# GNSS.net
KiCad netlist of a schematic drawn in Altium Designer
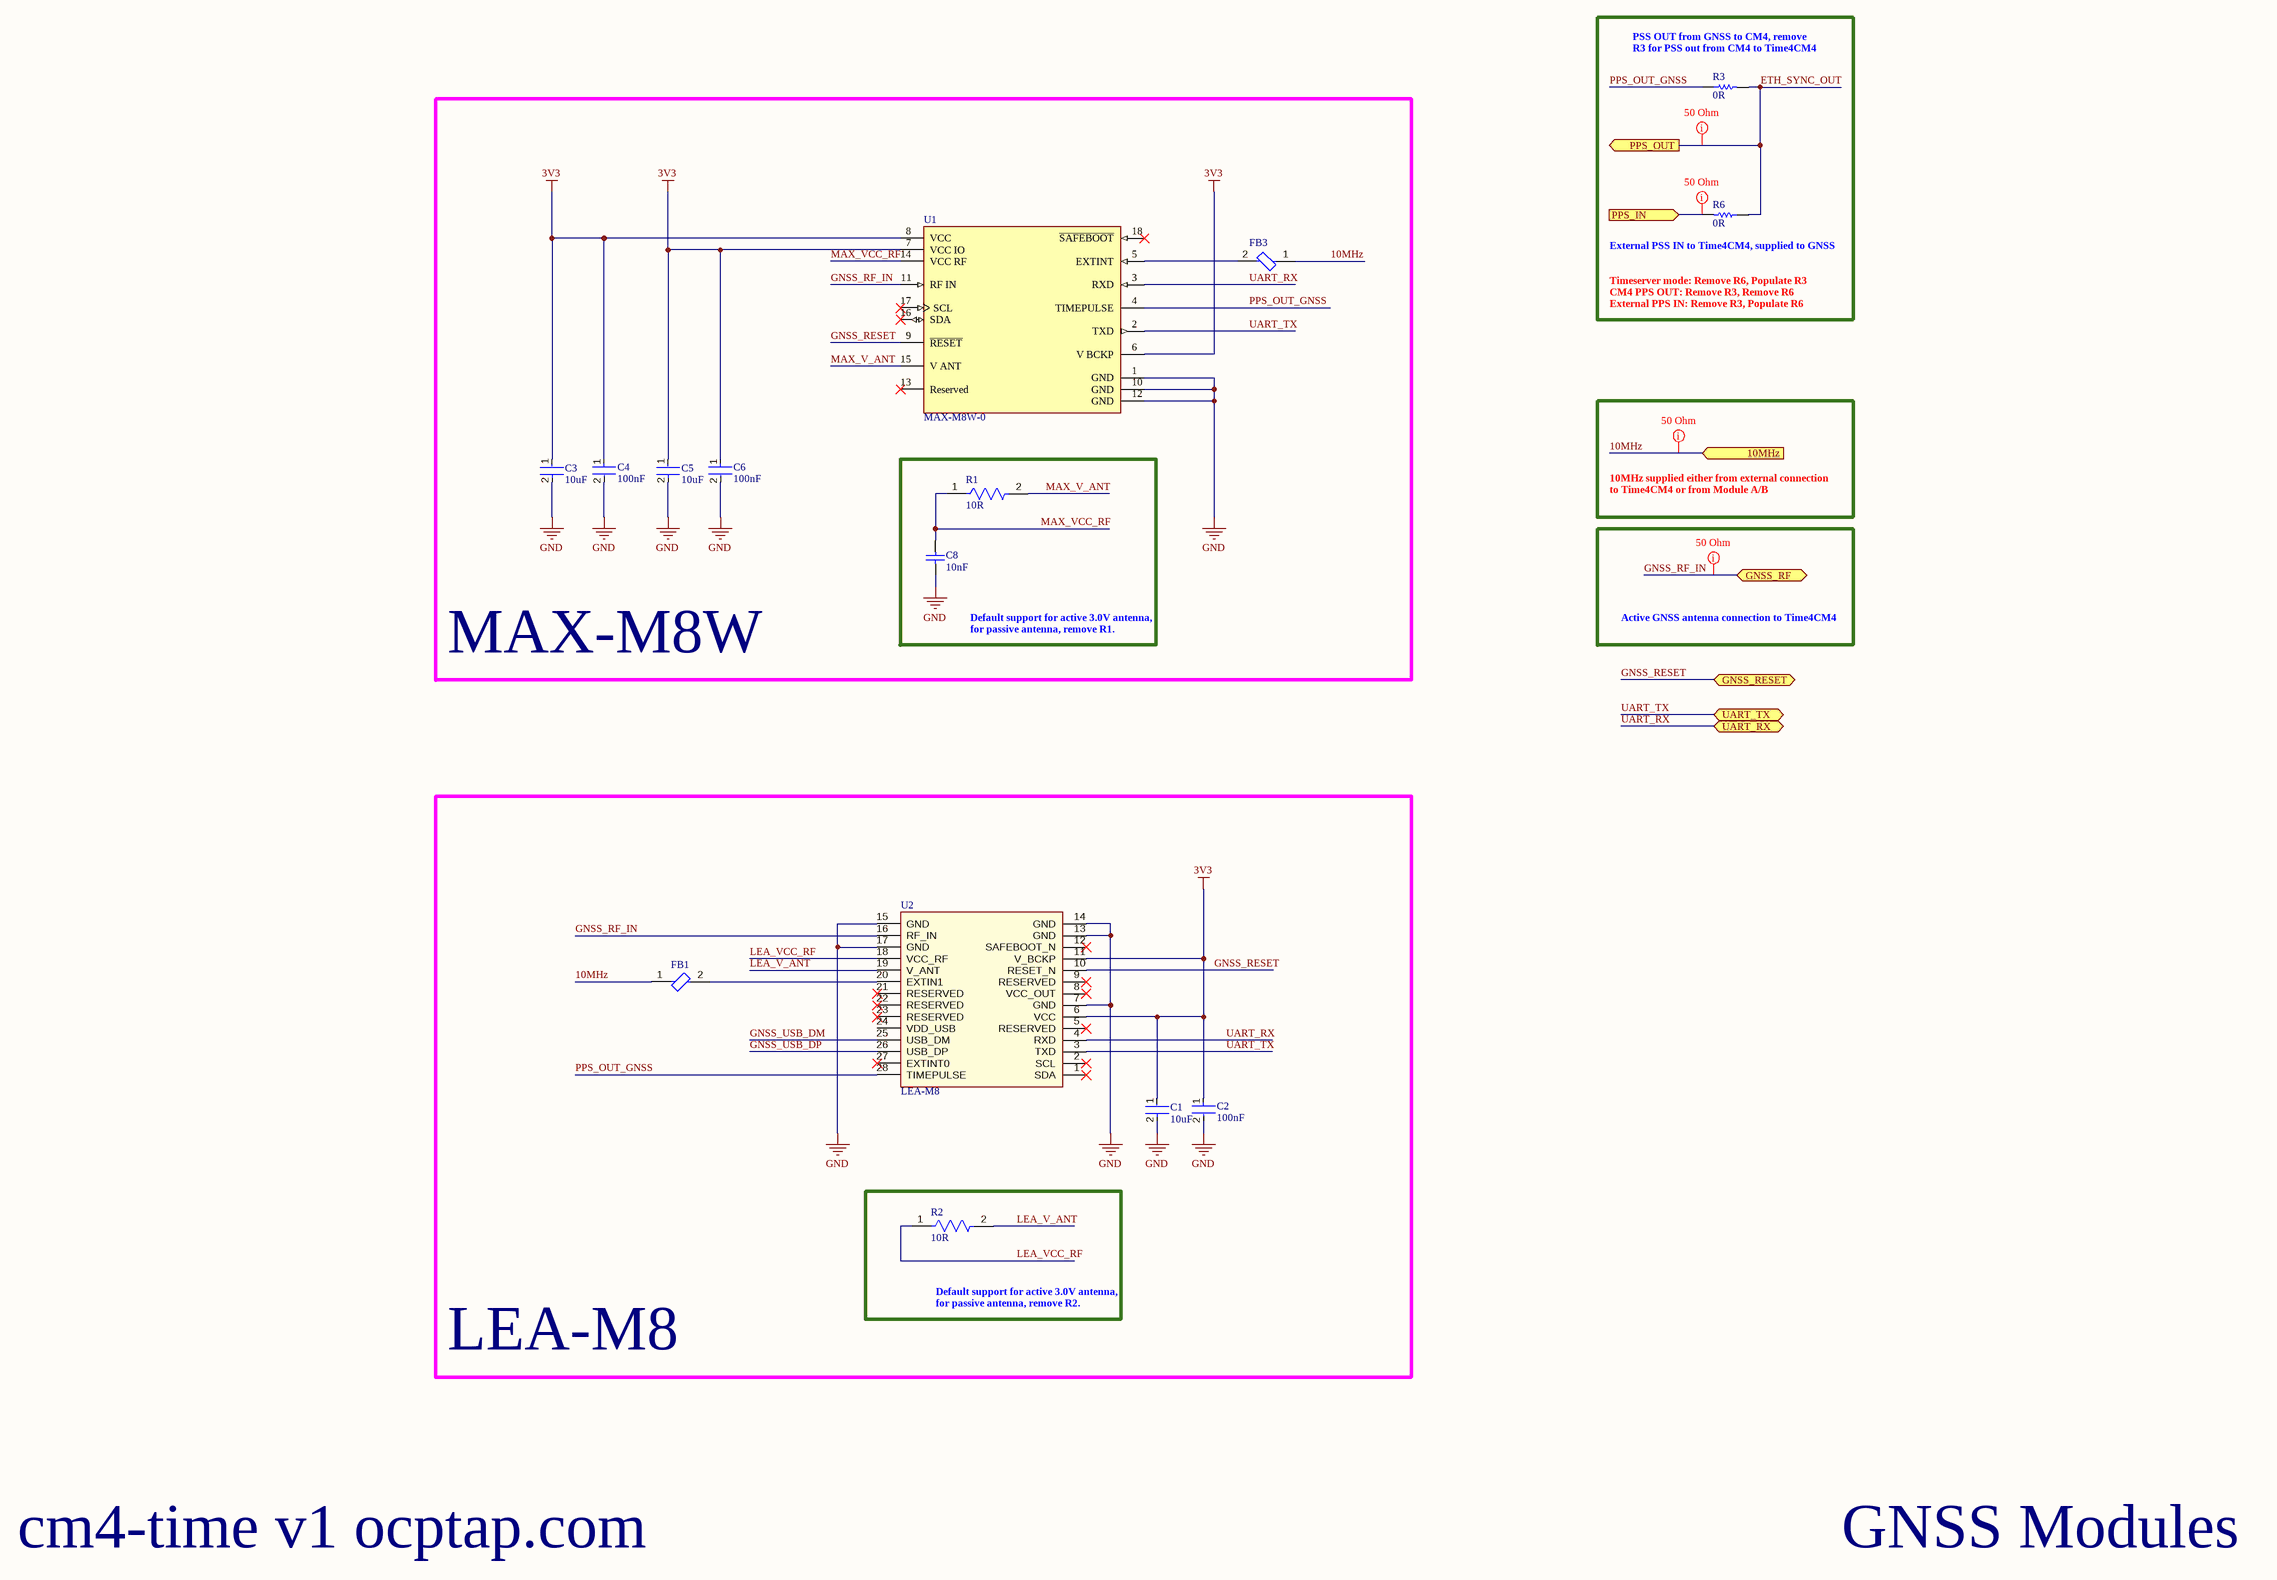
[diagram p0: GNSS.SchDoc]

(export (version "E")
  (design (tool "Eeschema 10.0.6"))
  (components
    (comp (ref "C1")
      (value "10uF")
      (footprint "FP-C1608-080-0_1-IPC_A")
      (description "Multilayer Ceramic Capacitors 10μF ±10% 10V X5R SMD 0603")
      (fields (field (name "VOLTAGE") "10V") (field (name "TOLERANCE") "10%"))
      (libsource (lib "Altium Content Vault") (part "236180d848d6139a670b325ea6854c9"))
    )
    (comp (ref "C2")
      (value "100nF")
      (footprint "FP-C0603C-CF-MFG")
      (description "CAP CER 0.1UF 50V 20% X7R 0603")
      (fields
        (field (name "MANUFACTURER PART NUMBER") "C0603C104M5RACTU")
        (field (name "MANUFACTURER") "KEMET")
      )
      (libsource (lib "Altium Content Vault") (part "b4654b650e69147ec39a6b967a45e02"))
    )
    (comp (ref "C3")
      (value "10uF")
      (footprint "FP-C1608-080-0_1-IPC_A")
      (description "Multilayer Ceramic Capacitors 10μF ±10% 10V X5R SMD 0603")
      (fields (field (name "VOLTAGE") "10V") (field (name "TOLERANCE") "10%"))
      (libsource (lib "Altium Content Vault") (part "236180d848d6139a670b325ea6854c9"))
    )
    (comp (ref "C4")
      (value "100nF")
      (footprint "FP-C0603C-CF-MFG")
      (description "CAP CER 0.1UF 50V 20% X7R 0603")
      (fields
        (field (name "MANUFACTURER PART NUMBER") "C0603C104M5RACTU")
        (field (name "MANUFACTURER") "KEMET")
      )
      (libsource (lib "Altium Content Vault") (part "b4654b650e69147ec39a6b967a45e02"))
    )
    (comp (ref "C5")
      (value "10uF")
      (footprint "FP-C1608-080-0_1-IPC_A")
      (description "Multilayer Ceramic Capacitors 10μF ±10% 10V X5R SMD 0603")
      (fields (field (name "VOLTAGE") "10V") (field (name "TOLERANCE") "10%"))
      (libsource (lib "Altium Content Vault") (part "236180d848d6139a670b325ea6854c9"))
    )
    (comp (ref "C6")
      (value "100nF")
      (footprint "FP-C0603C-CF-MFG")
      (description "CAP CER 0.1UF 50V 20% X7R 0603")
      (fields
        (field (name "MANUFACTURER PART NUMBER") "C0603C104M5RACTU")
        (field (name "MANUFACTURER") "KEMET")
      )
      (libsource (lib "Altium Content Vault") (part "b4654b650e69147ec39a6b967a45e02"))
    )
    (comp (ref "C8")
      (value "10nF")
      (footprint "CAPC1608X90X35LL15T15")
      (description "Multilayer Ceramic Capacitor, 0.01 uF, 16 V, ± 10%, X7R, 0603 [1608 Metric]")
      (fields
        (field (name "MANUFACTURER") "AVX Interconnect / Elco")
        (field (name "PART NUMBER") "0603YC103KAT2A")
      )
      (libsource (lib "Altium Content Vault") (part "CAP"))
    )
    (comp (ref "FB1")
      (value "BLM18HG102SH1D")
      (footprint "FP-BLM18-0_15-t0_8-IPC_C")
      (description "Chip Ferrite Bead, 0603, 1000Ω @ 100MHz, 1.6Ω, 25%, 100mA")
      (fields (field (name "TOLERANCE") "25%"))
      (libsource (lib "Altium Content Vault") (part "5f30dd21d616792df468990f7003faa"))
    )
    (comp (ref "FB3")
      (value "BLM18HG102SH1D")
      (footprint "FP-BLM18-0_15-t0_8-IPC_C")
      (description "Chip Ferrite Bead, 0603, 1000Ω @ 100MHz, 1.6Ω, 25%, 100mA")
      (fields (field (name "TOLERANCE") "25%"))
      (libsource (lib "Altium Content Vault") (part "5f30dd21d616792df468990f7003faa"))
    )
    (comp (ref "R1")
      (value "10R")
      (footprint "FP-ERJ3EK-MFG")
      (description "RES SMD 10 OHM 1% 1/10W 0603")
      (fields
        (field (name "OCTOPART") "https://octopart.com/erj-3ekf10r0v-panasonic-55403649")
        (field (name "MANUFACTURER PART NUMBER") "ERJ-3EKF10R0V")
      )
      (libsource (lib "Altium Content Vault") (part "1029c3af85768c4190bb7ad29bc67b5"))
    )
    (comp (ref "R2")
      (value "10R")
      (footprint "FP-ERJ3EK-MFG")
      (description "RES SMD 10 OHM 1% 1/10W 0603")
      (fields
        (field (name "OCTOPART") "https://octopart.com/erj-3ekf10r0v-panasonic-55403649")
        (field (name "MANUFACTURER PART NUMBER") "ERJ-3EKF10R0V")
      )
      (libsource (lib "Altium Content Vault") (part "1029c3af85768c4190bb7ad29bc67b5"))
    )
    (comp (ref "R3")
      (value "0R")
      (footprint "RESC1608X55X25ML10T15")
      (description "Chip Resistor, 0 Ohm, +/- 5%, 0.1 W, -55 to 155 degC, 0603 (1608 Metric), RoHS, Tape and Reel")
      (fields (field (name "TOLERANCE") "5%") (field (name "MANUFACTURER") "Yageo"))
      (libsource (lib "Altium Content Vault") (part "RES-2"))
    )
    (comp (ref "R6")
      (value "0R")
      (footprint "RESC1608X55X25ML10T15")
      (description "Chip Resistor, 0 Ohm, +/- 5%, 0.1 W, -55 to 155 degC, 0603 (1608 Metric), RoHS, Tape and Reel")
      (fields (field (name "TOLERANCE") "5%") (field (name "MANUFACTURER") "Yageo"))
      (libsource (lib "Altium Content Vault") (part "RES-2"))
    )
    (comp (ref "U1")
      (value "MAX-M8W-0")
      (footprint "FP-MAX-M8W-0-MFG")
      (description "RF RCVR GNSS/GPS 1.575GHZ 18LCC")
      (libsource (lib "Altium Content Vault") (part "36e94f557bbf38d877319147cff7e99"))
    )
    (comp (ref "U2")
      (value "LEA-M8")
      (footprint "LEA")
      (description "u-blox LEA GNSS module")
      (fields (field (name "MANUFACTURER") "u-blox"))
      (libsource (lib "ubloxLib") (part "LEA"))
    )
  )
  (nets
    (net (code "1") (name "/10MHz") (class "Default")
      (node (ref "FB1") (pin "1") (pinfunction "1_1") (pintype "passive"))
      (node (ref "FB3") (pin "1") (pinfunction "1_1") (pintype "passive"))
    )
    (net (code "2") (name "/ETH_SYNC_OUT") (class "Default")
      (node (ref "R3") (pin "2") (pinfunction "2_2") (pintype "passive"))
      (node (ref "R6") (pin "1") (pinfunction "1_1") (pintype "passive"))
    )
    (net (code "3") (name "/GNSS_RESET") (class "Default")
      (node (ref "U1") (pin "9") (pinfunction "~{RESET}_9") (pintype "passive"))
      (node (ref "U2") (pin "10") (pinfunction "RESET_N_10") (pintype "passive"))
    )
    (net (code "4") (name "/GNSS_RF_IN") (class "Default")
      (node (ref "U1") (pin "11") (pinfunction "RF_IN_11") (pintype "input"))
      (node (ref "U2") (pin "16") (pinfunction "RF_IN_16") (pintype "passive"))
    )
    (net (code "5") (name "/GNSS_USB_DM") (class "Default")
      (node (ref "U2") (pin "25") (pinfunction "USB_DM_25") (pintype "passive"))
    )
    (net (code "6") (name "/GNSS_USB_DP") (class "Default")
      (node (ref "U2") (pin "26") (pinfunction "USB_DP_26") (pintype "passive"))
    )
    (net (code "7") (name "/LEA_VCC_RF") (class "Default")
      (node (ref "R2") (pin "1") (pinfunction "1_1") (pintype "passive"))
      (node (ref "U2") (pin "18") (pinfunction "VCC_RF_18") (pintype "passive"))
    )
    (net (code "8") (name "/LEA_V_ANT") (class "Default")
      (node (ref "R2") (pin "2") (pinfunction "2_2") (pintype "passive"))
      (node (ref "U2") (pin "19") (pinfunction "V_ANT_19") (pintype "passive"))
    )
    (net (code "9") (name "/MAX_VCC_RF") (class "Default")
      (node (ref "C8") (pin "2") (pinfunction "2_2") (pintype "passive"))
      (node (ref "R1") (pin "1") (pinfunction "1_1") (pintype "passive"))
      (node (ref "U1") (pin "14") (pinfunction "VCC_RF_14") (pintype "power_in"))
    )
    (net (code "10") (name "/MAX_V_ANT") (class "Default")
      (node (ref "R1") (pin "2") (pinfunction "2_2") (pintype "passive"))
      (node (ref "U1") (pin "15") (pinfunction "V_ANT_15") (pintype "power_in"))
    )
    (net (code "11") (name "/PPS_IN") (class "Default")
      (node (ref "R6") (pin "2") (pinfunction "2_2") (pintype "passive"))
    )
    (net (code "12") (name "/PPS_OUT_GNSS") (class "Default")
      (node (ref "R3") (pin "1") (pinfunction "1_1") (pintype "passive"))
      (node (ref "U1") (pin "4") (pinfunction "TIMEPULSE_4") (pintype "passive"))
      (node (ref "U2") (pin "28") (pinfunction "TIMEPULSE_28") (pintype "passive"))
    )
    (net (code "13") (name "/UART_RX") (class "Default")
      (node (ref "U1") (pin "3") (pinfunction "RXD_3") (pintype "input"))
      (node (ref "U2") (pin "4") (pinfunction "RXD_4") (pintype "passive"))
    )
    (net (code "14") (name "/UART_TX") (class "Default")
      (node (ref "U1") (pin "2") (pinfunction "TXD_2") (pintype "output"))
      (node (ref "U2") (pin "3") (pinfunction "TXD_3") (pintype "passive"))
    )
    (net (code "15") (name "3V3") (class "Default")
      (node (ref "C1") (pin "1") (pinfunction "1_1") (pintype "passive"))
      (node (ref "C2") (pin "1") (pinfunction "1_1") (pintype "passive"))
      (node (ref "C3") (pin "1") (pinfunction "1_1") (pintype "passive"))
      (node (ref "C4") (pin "1") (pinfunction "1_1") (pintype "passive"))
      (node (ref "C5") (pin "1") (pinfunction "1_1") (pintype "passive"))
      (node (ref "C6") (pin "1") (pinfunction "1_1") (pintype "passive"))
      (node (ref "U1") (pin "6") (pinfunction "V_BCKP_6") (pintype "power_in"))
      (node (ref "U1") (pin "7") (pinfunction "VCC_IO_7") (pintype "power_in"))
      (node (ref "U1") (pin "8") (pinfunction "VCC_8") (pintype "power_in"))
      (node (ref "U2") (pin "11") (pinfunction "V_BCKP_11") (pintype "passive"))
      (node (ref "U2") (pin "6") (pinfunction "VCC_6") (pintype "passive"))
    )
    (net (code "16") (name "GND") (class "Default")
      (node (ref "C1") (pin "2") (pinfunction "2_2") (pintype "passive"))
      (node (ref "C2") (pin "2") (pinfunction "2_2") (pintype "passive"))
      (node (ref "C3") (pin "2") (pinfunction "2_2") (pintype "passive"))
      (node (ref "C4") (pin "2") (pinfunction "2_2") (pintype "passive"))
      (node (ref "C5") (pin "2") (pinfunction "2_2") (pintype "passive"))
      (node (ref "C6") (pin "2") (pinfunction "2_2") (pintype "passive"))
      (node (ref "C8") (pin "1") (pinfunction "1_1") (pintype "passive"))
      (node (ref "U1") (pin "1") (pinfunction "GND_1") (pintype "power_in"))
      (node (ref "U1") (pin "10") (pinfunction "GND_10") (pintype "power_in"))
      (node (ref "U1") (pin "12") (pinfunction "GND_12") (pintype "power_in"))
      (node (ref "U2") (pin "13") (pinfunction "GND_13") (pintype "passive"))
      (node (ref "U2") (pin "14") (pinfunction "GND_14") (pintype "passive"))
      (node (ref "U2") (pin "15") (pinfunction "GND_15") (pintype "passive"))
      (node (ref "U2") (pin "17") (pinfunction "GND_17") (pintype "passive"))
      (node (ref "U2") (pin "7") (pinfunction "GND_7") (pintype "passive"))
    )
    (net (code "17") (name "Net-(U1-EXTINT)") (class "Default")
      (node (ref "FB3") (pin "2") (pinfunction "2_2") (pintype "passive"))
      (node (ref "U1") (pin "5") (pinfunction "EXTINT_5") (pintype "input"))
    )
    (net (code "18") (name "Net-(U2-EXTIN1)") (class "Default")
      (node (ref "FB1") (pin "2") (pinfunction "2_2") (pintype "passive"))
      (node (ref "U2") (pin "20") (pinfunction "EXTIN1_20") (pintype "passive"))
    )
    (net (code "19") (name "unconnected-(U1-Reserved-Pad13)") (class "Default")
      (node (ref "U1") (pin "13") (pinfunction "Reserved_13") (pintype "passive+no_connect"))
    )
    (net (code "20") (name "unconnected-(U1-SCL-Pad17)") (class "Default")
      (node (ref "U1") (pin "17") (pinfunction "SCL_17") (pintype "input+no_connect"))
    )
    (net (code "21") (name "unconnected-(U1-SDA-Pad16)") (class "Default")
      (node (ref "U1") (pin "16") (pinfunction "SDA_16") (pintype "bidirectional+no_connect"))
    )
    (net (code "22") (name "unconnected-(U1-~{SAFEBOOT}-Pad18)") (class "Default")
      (node (ref "U1") (pin "18") (pinfunction "~{SAFEBOOT}_18") (pintype "input+no_connect"))
    )
    (net (code "23") (name "unconnected-(U2-EXTINT0-Pad27)") (class "Default")
      (node (ref "U2") (pin "27") (pinfunction "EXTINT0_27") (pintype "passive+no_connect"))
    )
    (net (code "24") (name "unconnected-(U2-RESERVED-Pad5)") (class "Default")
      (node (ref "U2") (pin "5") (pinfunction "RESERVED_5") (pintype "passive+no_connect"))
    )
    (net (code "25") (name "unconnected-(U2-RESERVED-Pad9)") (class "Default")
      (node (ref "U2") (pin "9") (pinfunction "RESERVED_9") (pintype "passive+no_connect"))
    )
    (net (code "26") (name "unconnected-(U2-RESERVED-Pad21)") (class "Default")
      (node (ref "U2") (pin "21") (pinfunction "RESERVED_21") (pintype "passive+no_connect"))
    )
    (net (code "27") (name "unconnected-(U2-RESERVED-Pad22)") (class "Default")
      (node (ref "U2") (pin "22") (pinfunction "RESERVED_22") (pintype "passive+no_connect"))
    )
    (net (code "28") (name "unconnected-(U2-RESERVED-Pad23)") (class "Default")
      (node (ref "U2") (pin "23") (pinfunction "RESERVED_23") (pintype "passive+no_connect"))
    )
    (net (code "29") (name "unconnected-(U2-SAFEBOOT_N-Pad12)") (class "Default")
      (node (ref "U2") (pin "12") (pinfunction "SAFEBOOT_N_12") (pintype "passive+no_connect"))
    )
    (net (code "30") (name "unconnected-(U2-SCL-Pad2)") (class "Default")
      (node (ref "U2") (pin "2") (pinfunction "SCL_2") (pintype "passive+no_connect"))
    )
    (net (code "31") (name "unconnected-(U2-SDA-Pad1)") (class "Default")
      (node (ref "U2") (pin "1") (pinfunction "SDA_1") (pintype "passive+no_connect"))
    )
    (net (code "32") (name "unconnected-(U2-VCC_OUT-Pad8)") (class "Default")
      (node (ref "U2") (pin "8") (pinfunction "VCC_OUT_8") (pintype "passive+no_connect"))
    )
    (net (code "33") (name "unconnected-(U2-VDD_USB-Pad24)") (class "Default")
      (node (ref "U2") (pin "24") (pinfunction "VDD_USB_24") (pintype "passive"))
    )
  )
)
